# STM32-ROMI_Rev_A_1_STM32.net
KiCad netlist of a schematic drawn in Altium Designer
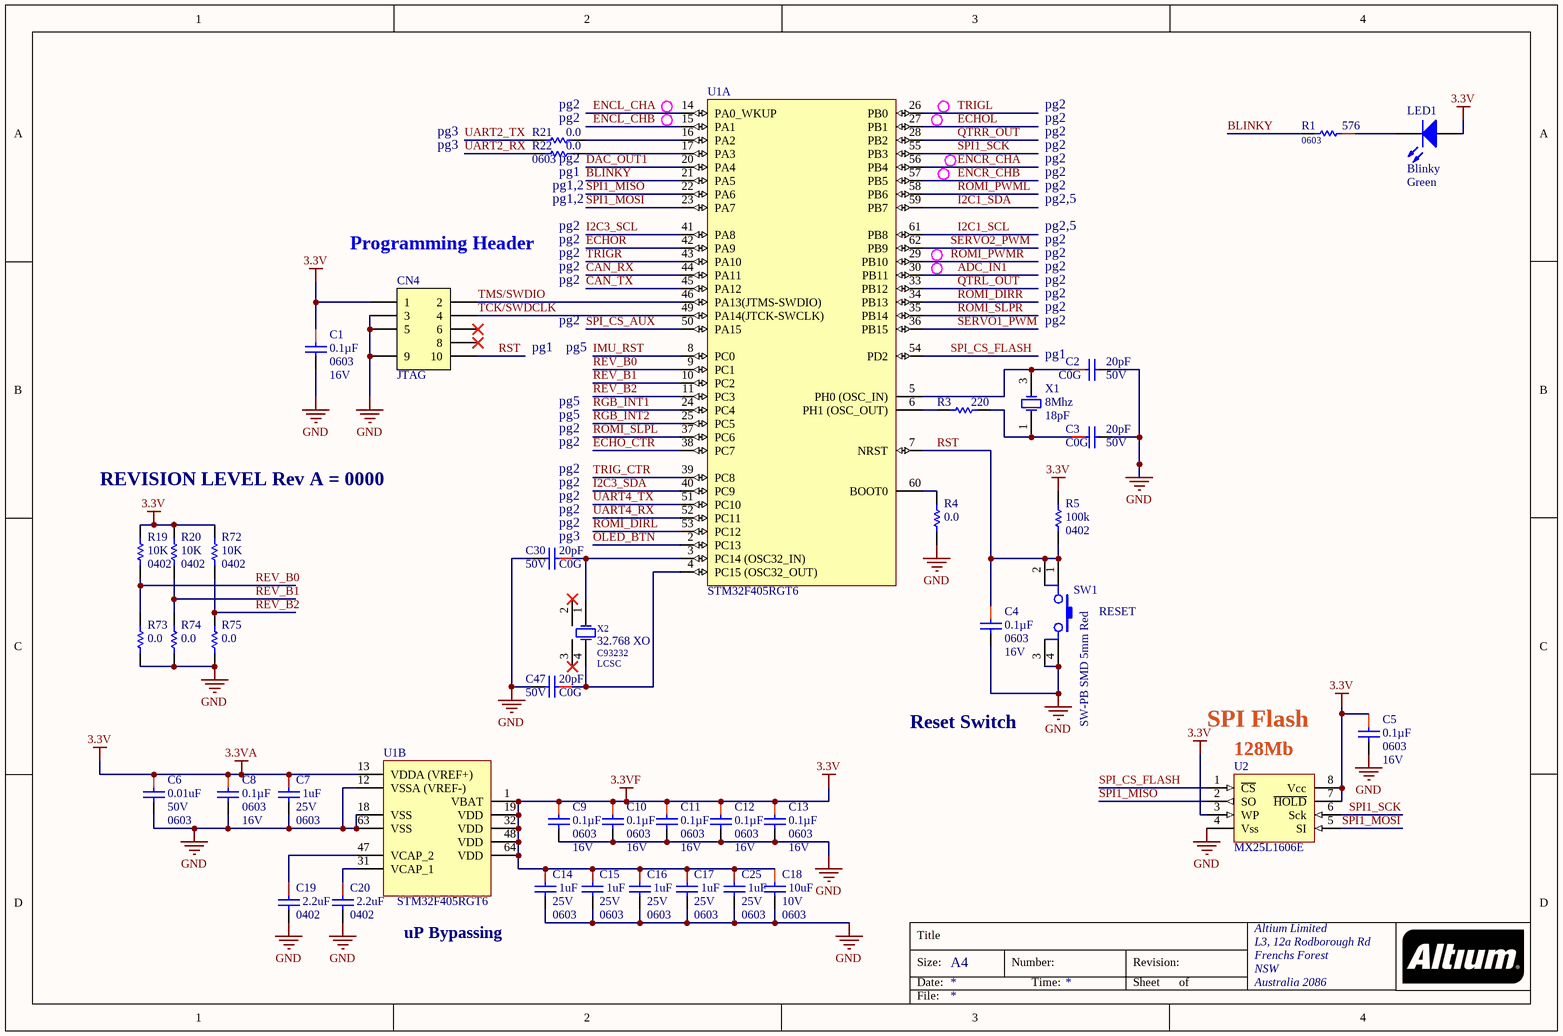
[diagram p0: STM32-ROMI_Rev_A_1_STM32.SchDoc]

(export (version "E")
  (design (tool "Eeschema 10.0.6"))
  (components
    (comp (ref "C1")
      (value "0.1uF")
      (footprint "CAPC0603(1608)_L")
      (description "0.1uF 0603 16V")
      (fields
        (field (name "MANUFACTURER") "Kemet")
        (field (name "MANUFACTURER PART NUMBER") "C0603C104K4RACTU")
        (field (name "CAPACITANCE") "0.1µF")
        (field (name "PACKAGE / CASE") "0603")
        (field (name "VOLTAGE - RATED") "16V")
      )
      (libsource (lib "JLCPCB_Passives") (part "CAP CER 0.1UF 16V 10% X7R 0603"))
    )
    (comp (ref "C2")
      (value "20pF 0402")
      (footprint "CAPC0402(1005)_L")
      (fields
        (field (name "MANUFACTURER") "Murata Electronics North America")
        (field (name "MANUFACTURER PART NUMBER") "GRM1555C1H200GA01D")
        (field (name "VOLTAGE - RATED") "50V")
        (field (name "TEMPERATURE COEFFICIENT") "C0G")
        (field (name "CAPACITANCE") "20pF")
        (field (name "TOLERANCE") "±2%")
        (field (name "CREATOR") "osman")
      )
      (libsource (lib "OLogic-Passive") (part "CAP CER 20PF 50V 2% NP0 0402"))
    )
    (comp (ref "C3")
      (value "20pF 0402")
      (footprint "CAPC0402(1005)_L")
      (fields
        (field (name "MANUFACTURER") "Murata Electronics North America")
        (field (name "MANUFACTURER PART NUMBER") "GRM1555C1H200GA01D")
        (field (name "VOLTAGE - RATED") "50V")
        (field (name "TEMPERATURE COEFFICIENT") "C0G")
        (field (name "CAPACITANCE") "20pF")
        (field (name "TOLERANCE") "±2%")
        (field (name "CREATOR") "osman")
      )
      (libsource (lib "OLogic-Passive") (part "CAP CER 20PF 50V 2% NP0 0402"))
    )
    (comp (ref "C4")
      (value "0.1uF")
      (footprint "CAPC0603(1608)_L")
      (description "0.1uF 0603 16V")
      (fields
        (field (name "MANUFACTURER") "Kemet")
        (field (name "MANUFACTURER PART NUMBER") "C0603C104K4RACTU")
        (field (name "CAPACITANCE") "0.1µF")
        (field (name "PACKAGE / CASE") "0603")
        (field (name "VOLTAGE - RATED") "16V")
      )
      (libsource (lib "JLCPCB_Passives") (part "CAP CER 0.1UF 16V 10% X7R 0603"))
    )
    (comp (ref "C5")
      (value "0.1uF")
      (footprint "CAPC0603(1608)_L")
      (description "0.1uF 0603 16V")
      (fields
        (field (name "MANUFACTURER") "Kemet")
        (field (name "MANUFACTURER PART NUMBER") "C0603C104K4RACTU")
        (field (name "CAPACITANCE") "0.1µF")
        (field (name "PACKAGE / CASE") "0603")
        (field (name "VOLTAGE - RATED") "16V")
      )
      (libsource (lib "JLCPCB_Passives") (part "CAP CER 0.1UF 16V 10% X7R 0603"))
    )
    (comp (ref "C6")
      (value "0.01uF")
      (footprint "CAPC0603(1608)_L")
      (description "0.01uF 50V 0603")
      (fields
        (field (name "MANUFACTURER") "Kemet")
        (field (name "MANUFACTURER PART NUMBER") "C0603C103K5RACTU")
        (field (name "VOLTAGE - RATED") "50V")
        (field (name "PACKAGE / CASE") "0603")
      )
      (libsource (lib "OLogic-Passive") (part "CAP CER 0.01uF 50V 10% X7R 0603"))
    )
    (comp (ref "C7")
      (value "1uF")
      (footprint "CAPC0603(1608)_N")
      (description "1uF 0603 25V")
      (fields
        (field (name "MANUFACTURER") "TDK Corporation")
        (field (name "MANUFACTURER PART NUMBER") "CGA3E1X7R1E105K080AC")
        (field (name "VOLTAGE - RATED") "25V")
        (field (name "PACKAGE / CASE") "0603")
      )
      (libsource (lib "OLogic-Passive") (part "CAP CER 1UF 25V 10% X7R 0603"))
    )
    (comp (ref "C8")
      (value "0.1uF")
      (footprint "CAPC0603(1608)_L")
      (description "0.1uF 0603 16V")
      (fields
        (field (name "MANUFACTURER") "Kemet")
        (field (name "MANUFACTURER PART NUMBER") "C0603C104K4RACTU")
        (field (name "CAPACITANCE") "0.1µF")
        (field (name "PACKAGE / CASE") "0603")
        (field (name "VOLTAGE - RATED") "16V")
      )
      (libsource (lib "JLCPCB_Passives") (part "CAP CER 0.1UF 16V 10% X7R 0603"))
    )
    (comp (ref "C9")
      (value "0.1uF")
      (footprint "CAPC0603(1608)_L")
      (description "0.1uF 0603 16V")
      (fields
        (field (name "MANUFACTURER") "Kemet")
        (field (name "MANUFACTURER PART NUMBER") "C0603C104K4RACTU")
        (field (name "CAPACITANCE") "0.1µF")
        (field (name "PACKAGE / CASE") "0603")
        (field (name "VOLTAGE - RATED") "16V")
      )
      (libsource (lib "JLCPCB_Passives") (part "CAP CER 0.1UF 16V 10% X7R 0603"))
    )
    (comp (ref "C10")
      (value "0.1uF")
      (footprint "CAPC0603(1608)_L")
      (description "0.1uF 0603 16V")
      (fields
        (field (name "MANUFACTURER") "Kemet")
        (field (name "MANUFACTURER PART NUMBER") "C0603C104K4RACTU")
        (field (name "CAPACITANCE") "0.1µF")
        (field (name "PACKAGE / CASE") "0603")
        (field (name "VOLTAGE - RATED") "16V")
      )
      (libsource (lib "JLCPCB_Passives") (part "CAP CER 0.1UF 16V 10% X7R 0603"))
    )
    (comp (ref "C11")
      (value "0.1uF")
      (footprint "CAPC0603(1608)_L")
      (description "0.1uF 0603 16V")
      (fields
        (field (name "MANUFACTURER") "Kemet")
        (field (name "MANUFACTURER PART NUMBER") "C0603C104K4RACTU")
        (field (name "CAPACITANCE") "0.1µF")
        (field (name "PACKAGE / CASE") "0603")
        (field (name "VOLTAGE - RATED") "16V")
      )
      (libsource (lib "JLCPCB_Passives") (part "CAP CER 0.1UF 16V 10% X7R 0603"))
    )
    (comp (ref "C12")
      (value "0.1uF")
      (footprint "CAPC0603(1608)_L")
      (description "0.1uF 0603 16V")
      (fields
        (field (name "MANUFACTURER") "Kemet")
        (field (name "MANUFACTURER PART NUMBER") "C0603C104K4RACTU")
        (field (name "CAPACITANCE") "0.1µF")
        (field (name "PACKAGE / CASE") "0603")
        (field (name "VOLTAGE - RATED") "16V")
      )
      (libsource (lib "JLCPCB_Passives") (part "CAP CER 0.1UF 16V 10% X7R 0603"))
    )
    (comp (ref "C13")
      (value "0.1uF")
      (footprint "CAPC0603(1608)_L")
      (description "0.1uF 0603 16V")
      (fields
        (field (name "MANUFACTURER") "Kemet")
        (field (name "MANUFACTURER PART NUMBER") "C0603C104K4RACTU")
        (field (name "CAPACITANCE") "0.1µF")
        (field (name "PACKAGE / CASE") "0603")
        (field (name "VOLTAGE - RATED") "16V")
      )
      (libsource (lib "JLCPCB_Passives") (part "CAP CER 0.1UF 16V 10% X7R 0603"))
    )
    (comp (ref "C14")
      (value "1uF")
      (footprint "CAPC0603(1608)_N")
      (description "1uF 0603 25V")
      (fields
        (field (name "MANUFACTURER") "TDK Corporation")
        (field (name "MANUFACTURER PART NUMBER") "CGA3E1X7R1E105K080AC")
        (field (name "VOLTAGE - RATED") "25V")
        (field (name "PACKAGE / CASE") "0603")
      )
      (libsource (lib "OLogic-Passive") (part "CAP CER 1UF 25V 10% X7R 0603"))
    )
    (comp (ref "C15")
      (value "1uF")
      (footprint "CAPC0603(1608)_N")
      (description "1uF 0603 25V")
      (fields
        (field (name "MANUFACTURER") "TDK Corporation")
        (field (name "MANUFACTURER PART NUMBER") "CGA3E1X7R1E105K080AC")
        (field (name "VOLTAGE - RATED") "25V")
        (field (name "PACKAGE / CASE") "0603")
      )
      (libsource (lib "OLogic-Passive") (part "CAP CER 1UF 25V 10% X7R 0603"))
    )
    (comp (ref "C16")
      (value "1uF")
      (footprint "CAPC0603(1608)_N")
      (description "1uF 0603 25V")
      (fields
        (field (name "MANUFACTURER") "TDK Corporation")
        (field (name "MANUFACTURER PART NUMBER") "CGA3E1X7R1E105K080AC")
        (field (name "VOLTAGE - RATED") "25V")
        (field (name "PACKAGE / CASE") "0603")
      )
      (libsource (lib "OLogic-Passive") (part "CAP CER 1UF 25V 10% X7R 0603"))
    )
    (comp (ref "C17")
      (value "1uF")
      (footprint "CAPC0603(1608)_N")
      (description "1uF 0603 25V")
      (fields
        (field (name "MANUFACTURER") "TDK Corporation")
        (field (name "MANUFACTURER PART NUMBER") "CGA3E1X7R1E105K080AC")
        (field (name "VOLTAGE - RATED") "25V")
        (field (name "PACKAGE / CASE") "0603")
      )
      (libsource (lib "OLogic-Passive") (part "CAP CER 1UF 25V 10% X7R 0603"))
    )
    (comp (ref "C18")
      (value "10uF")
      (footprint "CAPC0603(1608)_L")
      (description "10uF 0603 10V")
      (fields
        (field (name "MANUFACTURER") "Taiyo Yuden")
        (field (name "MANUFACTURER PART NUMBER") "LMK107BBJ106MAHT")
        (field (name "VOLTAGE - RATED") "10V")
        (field (name "PACKAGE / CASE") "0603")
      )
      (libsource (lib "OLogic-Passive") (part "CAP CER 10UF 10V 20% X5R 0603"))
    )
    (comp (ref "C19")
      (value "2.2uF")
      (footprint "CAPC0402(1005)_L")
      (description "2.2uF 0402")
      (fields
        (field (name "MANUFACTURER") "TDK Corporation")
        (field (name "MANUFACTURER PART NUMBER") "C1005X5R1V225K050BC")
        (field (name "PACKAGE / CASE") "0402")
        (field (name "CREATOR") "osman")
      )
      (libsource (lib "OLogic-Passive") (part "CAP CER 2.2UF 35V 10% X5R 0402"))
    )
    (comp (ref "C20")
      (value "2.2uF")
      (footprint "CAPC0402(1005)_L")
      (description "2.2uF 0402")
      (fields
        (field (name "MANUFACTURER") "TDK Corporation")
        (field (name "MANUFACTURER PART NUMBER") "C1005X5R1V225K050BC")
        (field (name "PACKAGE / CASE") "0402")
        (field (name "CREATOR") "osman")
      )
      (libsource (lib "OLogic-Passive") (part "CAP CER 2.2UF 35V 10% X5R 0402"))
    )
    (comp (ref "C25")
      (value "1uF")
      (footprint "CAPC0603(1608)_N")
      (description "1uF 0603 25V")
      (fields
        (field (name "MANUFACTURER") "TDK Corporation")
        (field (name "MANUFACTURER PART NUMBER") "CGA3E1X7R1E105K080AC")
        (field (name "VOLTAGE - RATED") "25V")
        (field (name "PACKAGE / CASE") "0603")
      )
      (libsource (lib "OLogic-Passive") (part "CAP CER 1UF 25V 10% X7R 0603"))
    )
    (comp (ref "C30")
      (value "20pF 0402")
      (footprint "CAPC0402(1005)_L")
      (fields
        (field (name "MANUFACTURER") "Murata Electronics North America")
        (field (name "MANUFACTURER PART NUMBER") "GRM1555C1H200GA01D")
        (field (name "VOLTAGE - RATED") "50V")
        (field (name "TEMPERATURE COEFFICIENT") "C0G")
        (field (name "CAPACITANCE") "20pF")
        (field (name "TOLERANCE") "±2%")
        (field (name "CREATOR") "osman")
      )
      (libsource (lib "OLogic-Passive") (part "CAP CER 20PF 50V 2% NP0 0402"))
    )
    (comp (ref "C47")
      (value "20pF 0402")
      (footprint "CAPC0402(1005)_L")
      (fields
        (field (name "MANUFACTURER") "Murata Electronics North America")
        (field (name "MANUFACTURER PART NUMBER") "GRM1555C1H200GA01D")
        (field (name "VOLTAGE - RATED") "50V")
        (field (name "TEMPERATURE COEFFICIENT") "C0G")
        (field (name "CAPACITANCE") "20pF")
        (field (name "TOLERANCE") "±2%")
        (field (name "CREATOR") "osman")
      )
      (libsource (lib "OLogic-Passive") (part "CAP CER 20PF 50V 2% NP0 0402"))
    )
    (comp (ref "CN4")
      (value "JTAG")
      (footprint "BOBS FAVORITE DEBUG HDR")
      (description "SAMTEC - FTSH-105-01-L-DV - HEADER, 1.27MM, SMD, 10WAY")
      (fields (field (name "MANUFACTURER") "Samtec") (field (name "MPN") "FTSH-105-01-L-DV"))
      (libsource (lib "OLogic-Connectors") (part "CONN-2x5-SWD"))
    )
    (comp (ref "LED1")
      (value "Blinky")
      (footprint "SM-LED-0603")
      (description "LED GREEN CLEAR THIN 0603 SMD")
      (fields
        (field (name "MANUFACTURER") "Lite-On Inc")
        (field (name "MANUFACTURER PART NUMBER") "LTST-C191KGKT")
        (field (name "COLOR") "Green")
      )
      (libsource (lib "Kyle-Diode-Opto-LED") (part "LTST-C191KGKT"))
    )
    (comp (ref "R1")
      (value "576")
      (footprint "RESC0603(1608)_N")
      (description "576OHMS ±1% 1/10W 0603")
      (fields (field (name "MANUFACTURER PART NUMBER") "0603WAF5760T5E") (field (name "PART SIZE") "0603"))
      (libsource (lib "JLCPCB_Passives") (part "576"))
    )
    (comp (ref "R3")
      (value "220")
      (footprint "RESC0402(1005)_L")
      (description "220 0402")
      (fields
        (field (name "MANUFACTURER") "Panasonic Electronic Components")
        (field (name "MANUFACTURER PART NUMBER") "ERJ-2RKF2200X")
        (field (name "RESISTANCE (OHMS)") "220")
        (field (name "CREATOR") "osman")
      )
      (libsource (lib "OLogic-Passive") (part "RES 220 OHM 1% 1/10W 0402"))
    )
    (comp (ref "R4")
      (value "0")
      (footprint "RESC0402(1005)_L")
      (description "0.0 0402")
      (fields
        (field (name "MANUFACTURER") "Panasonic Electronic Components")
        (field (name "MANUFACTURER PART NUMBER") "ERJ-2GE0R00X")
        (field (name "RESISTANCE (OHMS)") "0.0")
        (field (name "CREATOR") "osman")
      )
      (libsource (lib "OLogic-Passive") (part "RES 0.0 OHM JUMPER 1/10W 0402"))
    )
    (comp (ref "R5")
      (value "100K 0402")
      (footprint "RESC0402(1005)_L")
      (fields
        (field (name "MANUFACTURER") "Yageo")
        (field (name "MANUFACTURER PART NUMBER") "RC0402FR-07100KL")
        (field (name "TOLERANCE") "±1%")
        (field (name "SUPPLIER DEVICE PACKAGE") "0402")
        (field (name "RESISTANCE (OHMS)") "100k")
      )
      (libsource (lib "OLogic-Passive") (part "RES 100K OHM 1% 1/16W 0402"))
    )
    (comp (ref "R19")
      (value "10K")
      (footprint "RESC0402(1005)_N")
      (description "10K 0402")
      (fields
        (field (name "MANUFACTURER") "Samsung Electro-Mechanics")
        (field (name "MANUFACTURER PART NUMBER") "RC1005F103CS")
        (field (name "SUPPLIER DEVICE PACKAGE") "0402")
      )
      (libsource (lib "OLogic-Passive") (part "RES 10K OHM 1% 1/16W 0402"))
    )
    (comp (ref "R20")
      (value "10K")
      (footprint "RESC0402(1005)_N")
      (description "10K 0402")
      (fields
        (field (name "MANUFACTURER") "Samsung Electro-Mechanics")
        (field (name "MANUFACTURER PART NUMBER") "RC1005F103CS")
        (field (name "SUPPLIER DEVICE PACKAGE") "0402")
      )
      (libsource (lib "OLogic-Passive") (part "RES 10K OHM 1% 1/16W 0402"))
    )
    (comp (ref "R21")
      (value "0 0603")
      (footprint "RESC0603(1608)_N")
      (fields
        (field (name "MANUFACTURER") "Vishay Dale")
        (field (name "MANUFACTURER PART NUMBER") "CRCW06030000Z0EAHP")
        (field (name "TOLERANCE") "Jumper")
        (field (name "RESISTANCE (OHMS)") "0.0")
      )
      (libsource (lib "OLogic-Passive") (part "RES 0.0 OHM 1/4W JUMP 0603 SMD"))
    )
    (comp (ref "R22")
      (value "0 0603")
      (footprint "RESC0603(1608)_N")
      (fields
        (field (name "MANUFACTURER") "Vishay Dale")
        (field (name "MANUFACTURER PART NUMBER") "CRCW06030000Z0EAHP")
        (field (name "TOLERANCE") "Jumper")
        (field (name "RESISTANCE (OHMS)") "0.0")
        (field (name "PACKAGE / CASE") "0603")
      )
      (libsource (lib "OLogic-Passive") (part "RES 0.0 OHM 1/4W JUMP 0603 SMD"))
    )
    (comp (ref "R72")
      (value "10K")
      (footprint "RESC0402(1005)_N")
      (description "10K 0402")
      (fields
        (field (name "MANUFACTURER") "Samsung Electro-Mechanics")
        (field (name "MANUFACTURER PART NUMBER") "RC1005F103CS")
        (field (name "SUPPLIER DEVICE PACKAGE") "0402")
      )
      (libsource (lib "OLogic-Passive") (part "RES 10K OHM 1% 1/16W 0402"))
    )
    (comp (ref "R73")
      (value "0")
      (footprint "RESC0402(1005)_L")
      (description "0.0 0402")
      (fields
        (field (name "MANUFACTURER") "Panasonic Electronic Components")
        (field (name "MANUFACTURER PART NUMBER") "ERJ-2GE0R00X")
        (field (name "RESISTANCE (OHMS)") "0.0")
        (field (name "CREATOR") "osman")
      )
      (libsource (lib "OLogic-Passive") (part "RES 0.0 OHM JUMPER 1/10W 0402"))
    )
    (comp (ref "R74")
      (value "0")
      (footprint "RESC0402(1005)_L")
      (description "0.0 0402")
      (fields
        (field (name "MANUFACTURER") "Panasonic Electronic Components")
        (field (name "MANUFACTURER PART NUMBER") "ERJ-2GE0R00X")
        (field (name "RESISTANCE (OHMS)") "0.0")
        (field (name "CREATOR") "osman")
      )
      (libsource (lib "OLogic-Passive") (part "RES 0.0 OHM JUMPER 1/10W 0402"))
    )
    (comp (ref "R75")
      (value "0")
      (footprint "RESC0402(1005)_L")
      (description "0.0 0402")
      (fields
        (field (name "MANUFACTURER") "Panasonic Electronic Components")
        (field (name "MANUFACTURER PART NUMBER") "ERJ-2GE0R00X")
        (field (name "RESISTANCE (OHMS)") "0.0")
        (field (name "CREATOR") "osman")
      )
      (libsource (lib "OLogic-Passive") (part "RES 0.0 OHM JUMPER 1/10W 0402"))
    )
    (comp (ref "SW1")
      (value "RESET")
      (footprint "SW TACT Red 6mm x 6mm")
      (description "SWITCH TACTILE SPST-NO 0.05A 12V")
      (fields
        (field (name "MANUFACTURER") "C&K Components")
        (field (name "MANUFACTURER PART NUMBER") "PTS645SK50SMTR92 LFS")
        (field (name "TEXT") "SW-PB SMD 5mm Red")
        (field (name "PUBLISHER") "Altium Limited")
      )
      (libsource (lib "OLogic-Switches") (part "SW-PB SMD 5mm Red"))
    )
    (comp (ref "U1")
      (value "STM32F405RGT6")
      (footprint "STM-LQFP64_N")
      (description "IC MCU 32BIT 1MB FLASH 64LQFP")
      (fields
        (field (name "MANUFACTURER") "STMicroelectronics")
        (field (name "MANUFACTURER PART NUMBER") "STM32F405RGT6")
      )
      (libsource (lib "OLogic-CPU-Memory") (part "STM32F405RGT6"))
    )
    (comp (ref "U2")
      (value "MX25L1606E")
      (footprint "SOG.050/8D")
      (description "16M NOR Flash")
      (fields (field (name "MANUFACTURER") "Macronix") (field (name "MPN") "MX25L1606EM2I-12G"))
      (libsource (lib "OLogic-CPU-Memory") (part "MX25L1606E"))
    )
    (comp (ref "X1")
      (value "8Mhz")
      (footprint "SMXOSC/5x3.2")
      (description "8Mhz ABM3 Parallel Load Crystal")
      (fields
        (field (name "MANUFACTURER") "Abracon Corporation")
        (field (name "MANUFACTURER PART NUMBER") "ABM3B-8.000MHZ-B2-T")
        (field (name "LOAD CAPACITANCE") "18pF")
      )
      (libsource (lib "OLogic-RF-Osc") (part "CRYSTAL 8MHZ ABM3"))
    )
    (comp (ref "X2")
      (value "32.768 XO")
      (footprint "OSCABS")
      (description "SMD CRYSTAL RESONATORS 32.768KHZ ±20PPM SMD-3215_2P ROHS")
      (fields (field (name "SUPPLIER PART NUMBER 2") "C93232") (field (name "SUPPLIER 2") "LCSC"))
      (libsource (lib "JLCPCB_RF-OSC") (part "DST310S 32.768KHz"))
    )
  )
  (nets
    (net (code "1") (name "/ADC_IN1") (class "Default")
      (node (ref "U1") (pin "30") (pinfunction "PB11_30") (pintype "bidirectional"))
    )
    (net (code "2") (name "/BLINKY") (class "Default")
      (node (ref "R1") (pin "2") (pinfunction "2_2") (pintype "passive"))
      (node (ref "U1") (pin "21") (pinfunction "PA5_21") (pintype "bidirectional"))
    )
    (net (code "3") (name "/CAN_RX") (class "Default")
      (node (ref "U1") (pin "44") (pinfunction "PA11_44") (pintype "bidirectional"))
    )
    (net (code "4") (name "/CAN_TX") (class "Default")
      (node (ref "U1") (pin "45") (pinfunction "PA12_45") (pintype "bidirectional"))
    )
    (net (code "5") (name "/DAC_OUT1") (class "Default")
      (node (ref "U1") (pin "20") (pinfunction "PA4_20") (pintype "bidirectional"))
    )
    (net (code "6") (name "/ECHOL") (class "Default")
      (node (ref "U1") (pin "27") (pinfunction "PB1_27") (pintype "bidirectional"))
    )
    (net (code "7") (name "/ECHOR") (class "Default")
      (node (ref "U1") (pin "42") (pinfunction "PA9_42") (pintype "bidirectional"))
    )
    (net (code "8") (name "/ECHO_CTR") (class "Default")
      (node (ref "U1") (pin "38") (pinfunction "PC7_38") (pintype "bidirectional"))
    )
    (net (code "9") (name "/ENCL_CHA") (class "Default")
      (node (ref "U1") (pin "14") (pinfunction "PA0_WKUP_14") (pintype "bidirectional"))
    )
    (net (code "10") (name "/ENCL_CHB") (class "Default")
      (node (ref "U1") (pin "15") (pinfunction "PA1_15") (pintype "bidirectional"))
    )
    (net (code "11") (name "/ENCR_CHA") (class "Default")
      (node (ref "U1") (pin "56") (pinfunction "PB4_56") (pintype "bidirectional"))
    )
    (net (code "12") (name "/ENCR_CHB") (class "Default")
      (node (ref "U1") (pin "57") (pinfunction "PB5_57") (pintype "bidirectional"))
    )
    (net (code "13") (name "/I2C1_SCL") (class "Default")
      (node (ref "U1") (pin "61") (pinfunction "PB8_61") (pintype "bidirectional"))
    )
    (net (code "14") (name "/I2C1_SDA") (class "Default")
      (node (ref "U1") (pin "59") (pinfunction "PB7_59") (pintype "bidirectional"))
    )
    (net (code "15") (name "/I2C3_SCL") (class "Default")
      (node (ref "U1") (pin "41") (pinfunction "PA8_41") (pintype "bidirectional"))
    )
    (net (code "16") (name "/I2C3_SDA") (class "Default")
      (node (ref "U1") (pin "40") (pinfunction "PC9_40") (pintype "bidirectional"))
    )
    (net (code "17") (name "/IMU_RST") (class "Default")
      (node (ref "U1") (pin "8") (pinfunction "PC0_8") (pintype "bidirectional"))
    )
    (net (code "18") (name "/OLED_BTN") (class "Default")
      (node (ref "U1") (pin "2") (pinfunction "PC13_2") (pintype "bidirectional"))
    )
    (net (code "19") (name "/QTRL_OUT") (class "Default")
      (node (ref "U1") (pin "33") (pinfunction "PB12_33") (pintype "bidirectional"))
    )
    (net (code "20") (name "/QTRR_OUT") (class "Default")
      (node (ref "U1") (pin "28") (pinfunction "PB2_28") (pintype "bidirectional"))
    )
    (net (code "21") (name "/REV_B0") (class "Default")
      (node (ref "R19") (pin "1") (pinfunction "1_1") (pintype "passive"))
      (node (ref "R73") (pin "2") (pinfunction "2_2") (pintype "passive"))
      (node (ref "U1") (pin "9") (pinfunction "PC1_9") (pintype "bidirectional"))
    )
    (net (code "22") (name "/REV_B1") (class "Default")
      (node (ref "R20") (pin "1") (pinfunction "1_1") (pintype "passive"))
      (node (ref "R74") (pin "2") (pinfunction "2_2") (pintype "passive"))
      (node (ref "U1") (pin "10") (pinfunction "PC2_10") (pintype "bidirectional"))
    )
    (net (code "23") (name "/REV_B2") (class "Default")
      (node (ref "R72") (pin "1") (pinfunction "1_1") (pintype "passive"))
      (node (ref "R75") (pin "2") (pinfunction "2_2") (pintype "passive"))
      (node (ref "U1") (pin "11") (pinfunction "PC3_11") (pintype "bidirectional"))
    )
    (net (code "24") (name "/RGB_INT1") (class "Default")
      (node (ref "U1") (pin "24") (pinfunction "PC4_24") (pintype "bidirectional"))
    )
    (net (code "25") (name "/RGB_INT2") (class "Default")
      (node (ref "U1") (pin "25") (pinfunction "PC5_25") (pintype "bidirectional"))
    )
    (net (code "26") (name "/ROMI_DIRL") (class "Default")
      (node (ref "U1") (pin "53") (pinfunction "PC12_53") (pintype "bidirectional"))
    )
    (net (code "27") (name "/ROMI_DIRR") (class "Default")
      (node (ref "U1") (pin "34") (pinfunction "PB13_34") (pintype "bidirectional"))
    )
    (net (code "28") (name "/ROMI_PWML") (class "Default")
      (node (ref "U1") (pin "58") (pinfunction "PB6_58") (pintype "bidirectional"))
    )
    (net (code "29") (name "/ROMI_PWMR") (class "Default")
      (node (ref "U1") (pin "29") (pinfunction "PB10_29") (pintype "bidirectional"))
    )
    (net (code "30") (name "/ROMI_~{SLPL}") (class "Default")
      (node (ref "U1") (pin "37") (pinfunction "PC6_37") (pintype "bidirectional"))
    )
    (net (code "31") (name "/ROMI_~{SLPR}") (class "Default")
      (node (ref "U1") (pin "35") (pinfunction "PB14_35") (pintype "bidirectional"))
    )
    (net (code "32") (name "/RST") (class "Default")
      (node (ref "C4") (pin "1") (pinfunction "1_1") (pintype "passive"))
      (node (ref "CN4") (pin "10") (pinfunction "10_10") (pintype "passive"))
      (node (ref "R5") (pin "1") (pinfunction "1_1") (pintype "passive"))
      (node (ref "SW1") (pin "1") (pinfunction "1_1") (pintype "passive"))
      (node (ref "SW1") (pin "2") (pinfunction "2_2") (pintype "passive"))
      (node (ref "U1") (pin "7") (pinfunction "NRST_7") (pintype "bidirectional"))
    )
    (net (code "33") (name "/SERVO1_PWM") (class "Default")
      (node (ref "U1") (pin "36") (pinfunction "PB15_36") (pintype "bidirectional"))
    )
    (net (code "34") (name "/SERVO2_PWM") (class "Default")
      (node (ref "U1") (pin "62") (pinfunction "PB9_62") (pintype "bidirectional"))
    )
    (net (code "35") (name "/SPI1_MISO") (class "Default")
      (node (ref "U1") (pin "22") (pinfunction "PA6_22") (pintype "bidirectional"))
      (node (ref "U2") (pin "2") (pinfunction "SO_2") (pintype "output"))
    )
    (net (code "36") (name "/SPI1_MOSI") (class "Default")
      (node (ref "U1") (pin "23") (pinfunction "PA7_23") (pintype "bidirectional"))
      (node (ref "U2") (pin "5") (pinfunction "SI_5") (pintype "input"))
    )
    (net (code "37") (name "/SPI1_SCK") (class "Default")
      (node (ref "U1") (pin "55") (pinfunction "PB3_55") (pintype "bidirectional"))
      (node (ref "U2") (pin "6") (pinfunction "Sck_6") (pintype "input"))
    )
    (net (code "38") (name "/SPI_CS_AUX") (class "Default")
      (node (ref "U1") (pin "50") (pinfunction "PA15_50") (pintype "bidirectional"))
    )
    (net (code "39") (name "/SPI_CS_FLASH") (class "Default")
      (node (ref "U1") (pin "54") (pinfunction "PD2_54") (pintype "bidirectional"))
      (node (ref "U2") (pin "1") (pinfunction "~{CS}_1") (pintype "input"))
    )
    (net (code "40") (name "/TCK{slash}SWDCLK") (class "Default")
      (node (ref "CN4") (pin "4") (pinfunction "4_4") (pintype "passive"))
      (node (ref "U1") (pin "49") (pinfunction "PA14(JTCK-SWCLK)_49") (pintype "bidirectional"))
    )
    (net (code "41") (name "/TMS{slash}SWDIO") (class "Default")
      (node (ref "CN4") (pin "2") (pinfunction "2_2") (pintype "passive"))
      (node (ref "U1") (pin "46") (pinfunction "PA13(JTMS-SWDIO)_46") (pintype "bidirectional"))
    )
    (net (code "42") (name "/TRIGL") (class "Default")
      (node (ref "U1") (pin "26") (pinfunction "PB0_26") (pintype "bidirectional"))
    )
    (net (code "43") (name "/TRIGR") (class "Default")
      (node (ref "U1") (pin "43") (pinfunction "PA10_43") (pintype "bidirectional"))
    )
    (net (code "44") (name "/TRIG_CTR") (class "Default")
      (node (ref "U1") (pin "39") (pinfunction "PC8_39") (pintype "bidirectional"))
    )
    (net (code "45") (name "/UART2_RX") (class "Default")
      (node (ref "R22") (pin "2") (pinfunction "2_2") (pintype "passive"))
    )
    (net (code "46") (name "/UART2_TX") (class "Default")
      (node (ref "R21") (pin "2") (pinfunction "2_2") (pintype "passive"))
    )
    (net (code "47") (name "/UART4_RX") (class "Default")
      (node (ref "U1") (pin "52") (pinfunction "PC11_52") (pintype "bidirectional"))
    )
    (net (code "48") (name "/UART4_TX") (class "Default")
      (node (ref "U1") (pin "51") (pinfunction "PC10_51") (pintype "bidirectional"))
    )
    (net (code "49") (name "3.3V") (class "Default")
      (node (ref "C1") (pin "1") (pinfunction "1_1") (pintype "passive"))
      (node (ref "C10") (pin "1") (pinfunction "1_1") (pintype "passive"))
      (node (ref "C11") (pin "1") (pinfunction "1_1") (pintype "passive"))
      (node (ref "C12") (pin "1") (pinfunction "1_1") (pintype "passive"))
      (node (ref "C13") (pin "1") (pinfunction "1_1") (pintype "passive"))
      (node (ref "C14") (pin "1") (pinfunction "1_1") (pintype "passive"))
      (node (ref "C15") (pin "1") (pinfunction "1_1") (pintype "passive"))
      (node (ref "C16") (pin "1") (pinfunction "1_1") (pintype "passive"))
      (node (ref "C17") (pin "1") (pinfunction "1_1") (pintype "passive"))
      (node (ref "C18") (pin "1") (pinfunction "1_1") (pintype "passive"))
      (node (ref "C25") (pin "1") (pinfunction "1_1") (pintype "passive"))
      (node (ref "C5") (pin "1") (pinfunction "1_1") (pintype "passive"))
      (node (ref "C6") (pin "1") (pinfunction "1_1") (pintype "passive"))
      (node (ref "C7") (pin "1") (pinfunction "1_1") (pintype "passive"))
      (node (ref "C8") (pin "1") (pinfunction "1_1") (pintype "passive"))
      (node (ref "C9") (pin "1") (pinfunction "1_1") (pintype "passive"))
      (node (ref "CN4") (pin "1") (pinfunction "1_1") (pintype "passive"))
      (node (ref "LED1") (pin "1") (pinfunction "1_1") (pintype "passive"))
      (node (ref "R19") (pin "2") (pinfunction "2_2") (pintype "passive"))
      (node (ref "R20") (pin "2") (pinfunction "2_2") (pintype "passive"))
      (node (ref "R5") (pin "2") (pinfunction "2_2") (pintype "passive"))
      (node (ref "R72") (pin "2") (pinfunction "2_2") (pintype "passive"))
      (node (ref "U1") (pin "1") (pinfunction "VBAT_1") (pintype "power_in"))
      (node (ref "U1") (pin "13") (pinfunction "VDDA_(VREF+)_13") (pintype "power_in"))
      (node (ref "U1") (pin "19") (pinfunction "VDD_19") (pintype "power_in"))
      (node (ref "U1") (pin "32") (pinfunction "VDD_32") (pintype "power_in"))
      (node (ref "U1") (pin "48") (pinfunction "VDD_48") (pintype "power_in"))
      (node (ref "U1") (pin "64") (pinfunction "VDD_64") (pintype "power_in"))
      (node (ref "U2") (pin "3") (pinfunction "WP_3") (pintype "input"))
      (node (ref "U2") (pin "7") (pinfunction "~{HOLD}_7") (pintype "passive"))
      (node (ref "U2") (pin "8") (pinfunction "Vcc_8") (pintype "power_in"))
    )
    (net (code "50") (name "GND") (class "Default")
      (node (ref "C1") (pin "2") (pinfunction "2_2") (pintype "passive"))
      (node (ref "C10") (pin "2") (pinfunction "2_2") (pintype "passive"))
      (node (ref "C11") (pin "2") (pinfunction "2_2") (pintype "passive"))
      (node (ref "C12") (pin "2") (pinfunction "2_2") (pintype "passive"))
      (node (ref "C13") (pin "2") (pinfunction "2_2") (pintype "passive"))
      (node (ref "C14") (pin "2") (pinfunction "2_2") (pintype "passive"))
      (node (ref "C15") (pin "2") (pinfunction "2_2") (pintype "passive"))
      (node (ref "C16") (pin "2") (pinfunction "2_2") (pintype "passive"))
      (node (ref "C17") (pin "2") (pinfunction "2_2") (pintype "passive"))
      (node (ref "C18") (pin "2") (pinfunction "2_2") (pintype "passive"))
      (node (ref "C19") (pin "2") (pinfunction "2_2") (pintype "passive"))
      (node (ref "C2") (pin "2") (pinfunction "2_2") (pintype "passive"))
      (node (ref "C20") (pin "2") (pinfunction "2_2") (pintype "passive"))
      (node (ref "C25") (pin "2") (pinfunction "2_2") (pintype "passive"))
      (node (ref "C3") (pin "2") (pinfunction "2_2") (pintype "passive"))
      (node (ref "C30") (pin "2") (pinfunction "2_2") (pintype "passive"))
      (node (ref "C4") (pin "2") (pinfunction "2_2") (pintype "passive"))
      (node (ref "C47") (pin "2") (pinfunction "2_2") (pintype "passive"))
      (node (ref "C5") (pin "2") (pinfunction "2_2") (pintype "passive"))
      (node (ref "C6") (pin "2") (pinfunction "2_2") (pintype "passive"))
      (node (ref "C7") (pin "2") (pinfunction "2_2") (pintype "passive"))
      (node (ref "C8") (pin "2") (pinfunction "2_2") (pintype "passive"))
      (node (ref "C9") (pin "2") (pinfunction "2_2") (pintype "passive"))
      (node (ref "CN4") (pin "3") (pinfunction "3_3") (pintype "passive"))
      (node (ref "CN4") (pin "5") (pinfunction "5_5") (pintype "passive"))
      (node (ref "CN4") (pin "9") (pinfunction "9_9") (pintype "passive"))
      (node (ref "R4") (pin "1") (pinfunction "1_1") (pintype "passive"))
      (node (ref "R73") (pin "1") (pinfunction "1_1") (pintype "passive"))
      (node (ref "R74") (pin "1") (pinfunction "1_1") (pintype "passive"))
      (node (ref "R75") (pin "1") (pinfunction "1_1") (pintype "passive"))
      (node (ref "SW1") (pin "3") (pinfunction "3_3") (pintype "passive"))
      (node (ref "SW1") (pin "4") (pinfunction "4_4") (pintype "passive"))
      (node (ref "U1") (pin "12") (pinfunction "VSSA_(VREF-)_12") (pintype "power_in"))
      (node (ref "U1") (pin "18") (pinfunction "VSS_18") (pintype "power_in"))
      (node (ref "U1") (pin "63") (pinfunction "VSS_63") (pintype "power_in"))
      (node (ref "U2") (pin "4") (pinfunction "Vss_4") (pintype "power_in"))
    )
    (net (code "51") (name "Net-(LED1-Pad2)") (class "Default")
      (node (ref "LED1") (pin "2") (pinfunction "2_2") (pintype "passive"))
      (node (ref "R1") (pin "1") (pinfunction "1_1") (pintype "passive"))
    )
    (net (code "52") (name "Net-(U1A-BOOT0)") (class "Default")
      (node (ref "R4") (pin "2") (pinfunction "2_2") (pintype "passive"))
      (node (ref "U1") (pin "60") (pinfunction "BOOT0_60") (pintype "passive"))
    )
    (net (code "53") (name "Net-(U1A-PA2)") (class "Default")
      (node (ref "R21") (pin "1") (pinfunction "1_1") (pintype "passive"))
      (node (ref "U1") (pin "16") (pinfunction "PA2_16") (pintype "bidirectional"))
    )
    (net (code "54") (name "Net-(U1A-PA3)") (class "Default")
      (node (ref "R22") (pin "1") (pinfunction "1_1") (pintype "passive"))
      (node (ref "U1") (pin "17") (pinfunction "PA3_17") (pintype "bidirectional"))
    )
    (net (code "55") (name "Net-(U1A-PC14_(OSC32_IN))") (class "Default")
      (node (ref "C30") (pin "1") (pinfunction "1_1") (pintype "passive"))
      (node (ref "U1") (pin "3") (pinfunction "PC14_(OSC32_IN)_3") (pintype "bidirectional"))
      (node (ref "X2") (pin "1") (pinfunction "OSC1_1") (pintype "passive"))
    )
    (net (code "56") (name "Net-(U1A-PC15_(OSC32_OUT))") (class "Default")
      (node (ref "C47") (pin "1") (pinfunction "1_1") (pintype "passive"))
      (node (ref "U1") (pin "4") (pinfunction "PC15_(OSC32_OUT)_4") (pintype "bidirectional"))
      (node (ref "X2") (pin "4") (pinfunction "OSC2_4") (pintype "passive"))
    )
    (net (code "57") (name "Net-(U1A-PH0_(OSC_IN))") (class "Default")
      (node (ref "C2") (pin "1") (pinfunction "1_1") (pintype "passive"))
      (node (ref "U1") (pin "5") (pinfunction "PH0_(OSC_IN)_5") (pintype "passive"))
      (node (ref "X1") (pin "3") (pinfunction "OSC2_3") (pintype "passive"))
    )
    (net (code "58") (name "Net-(U1A-PH1_(OSC_OUT))") (class "Default")
      (node (ref "R3") (pin "2") (pinfunction "2_2") (pintype "passive"))
      (node (ref "U1") (pin "6") (pinfunction "PH1_(OSC_OUT)_6") (pintype "passive"))
    )
    (net (code "59") (name "Net-(U1B-VCAP_1)") (class "Default")
      (node (ref "C20") (pin "1") (pinfunction "1_1") (pintype "passive"))
      (node (ref "U1") (pin "31") (pinfunction "VCAP_1_31") (pintype "passive"))
    )
    (net (code "60") (name "Net-(U1B-VCAP_2)") (class "Default")
      (node (ref "C19") (pin "1") (pinfunction "1_1") (pintype "passive"))
      (node (ref "U1") (pin "47") (pinfunction "VCAP_2_47") (pintype "passive"))
    )
    (net (code "61") (name "Net-(X1-OSC1)") (class "Default")
      (node (ref "C3") (pin "1") (pinfunction "1_1") (pintype "passive"))
      (node (ref "R3") (pin "1") (pinfunction "1_1") (pintype "passive"))
      (node (ref "X1") (pin "1") (pinfunction "OSC1_1") (pintype "passive"))
    )
    (net (code "62") (name "unconnected-(CN4-Pad6)") (class "Default")
      (node (ref "CN4") (pin "6") (pinfunction "6_6") (pintype "passive+no_connect"))
    )
    (net (code "63") (name "unconnected-(CN4-Pad8)") (class "Default")
      (node (ref "CN4") (pin "8") (pinfunction "8_8") (pintype "passive+no_connect"))
    )
    (net (code "64") (name "unconnected-(X1-NC-Pad2)") (class "Default")
      (node (ref "X1") (pin "2") (pinfunction "NC_2") (pintype "passive"))
    )
    (net (code "65") (name "unconnected-(X1-NC-Pad4)") (class "Default")
      (node (ref "X1") (pin "4") (pinfunction "NC_4") (pintype "passive"))
    )
    (net (code "66") (name "unconnected-(X2-NC-Pad2)") (class "Default")
      (node (ref "X2") (pin "2") (pinfunction "NC_2") (pintype "passive+no_connect"))
    )
    (net (code "67") (name "unconnected-(X2-NC-Pad3)") (class "Default")
      (node (ref "X2") (pin "3") (pinfunction "NC_3") (pintype "passive+no_connect"))
    )
  )
)
